# untitled.net
KiCad netlist of a schematic drawn in EAGLE
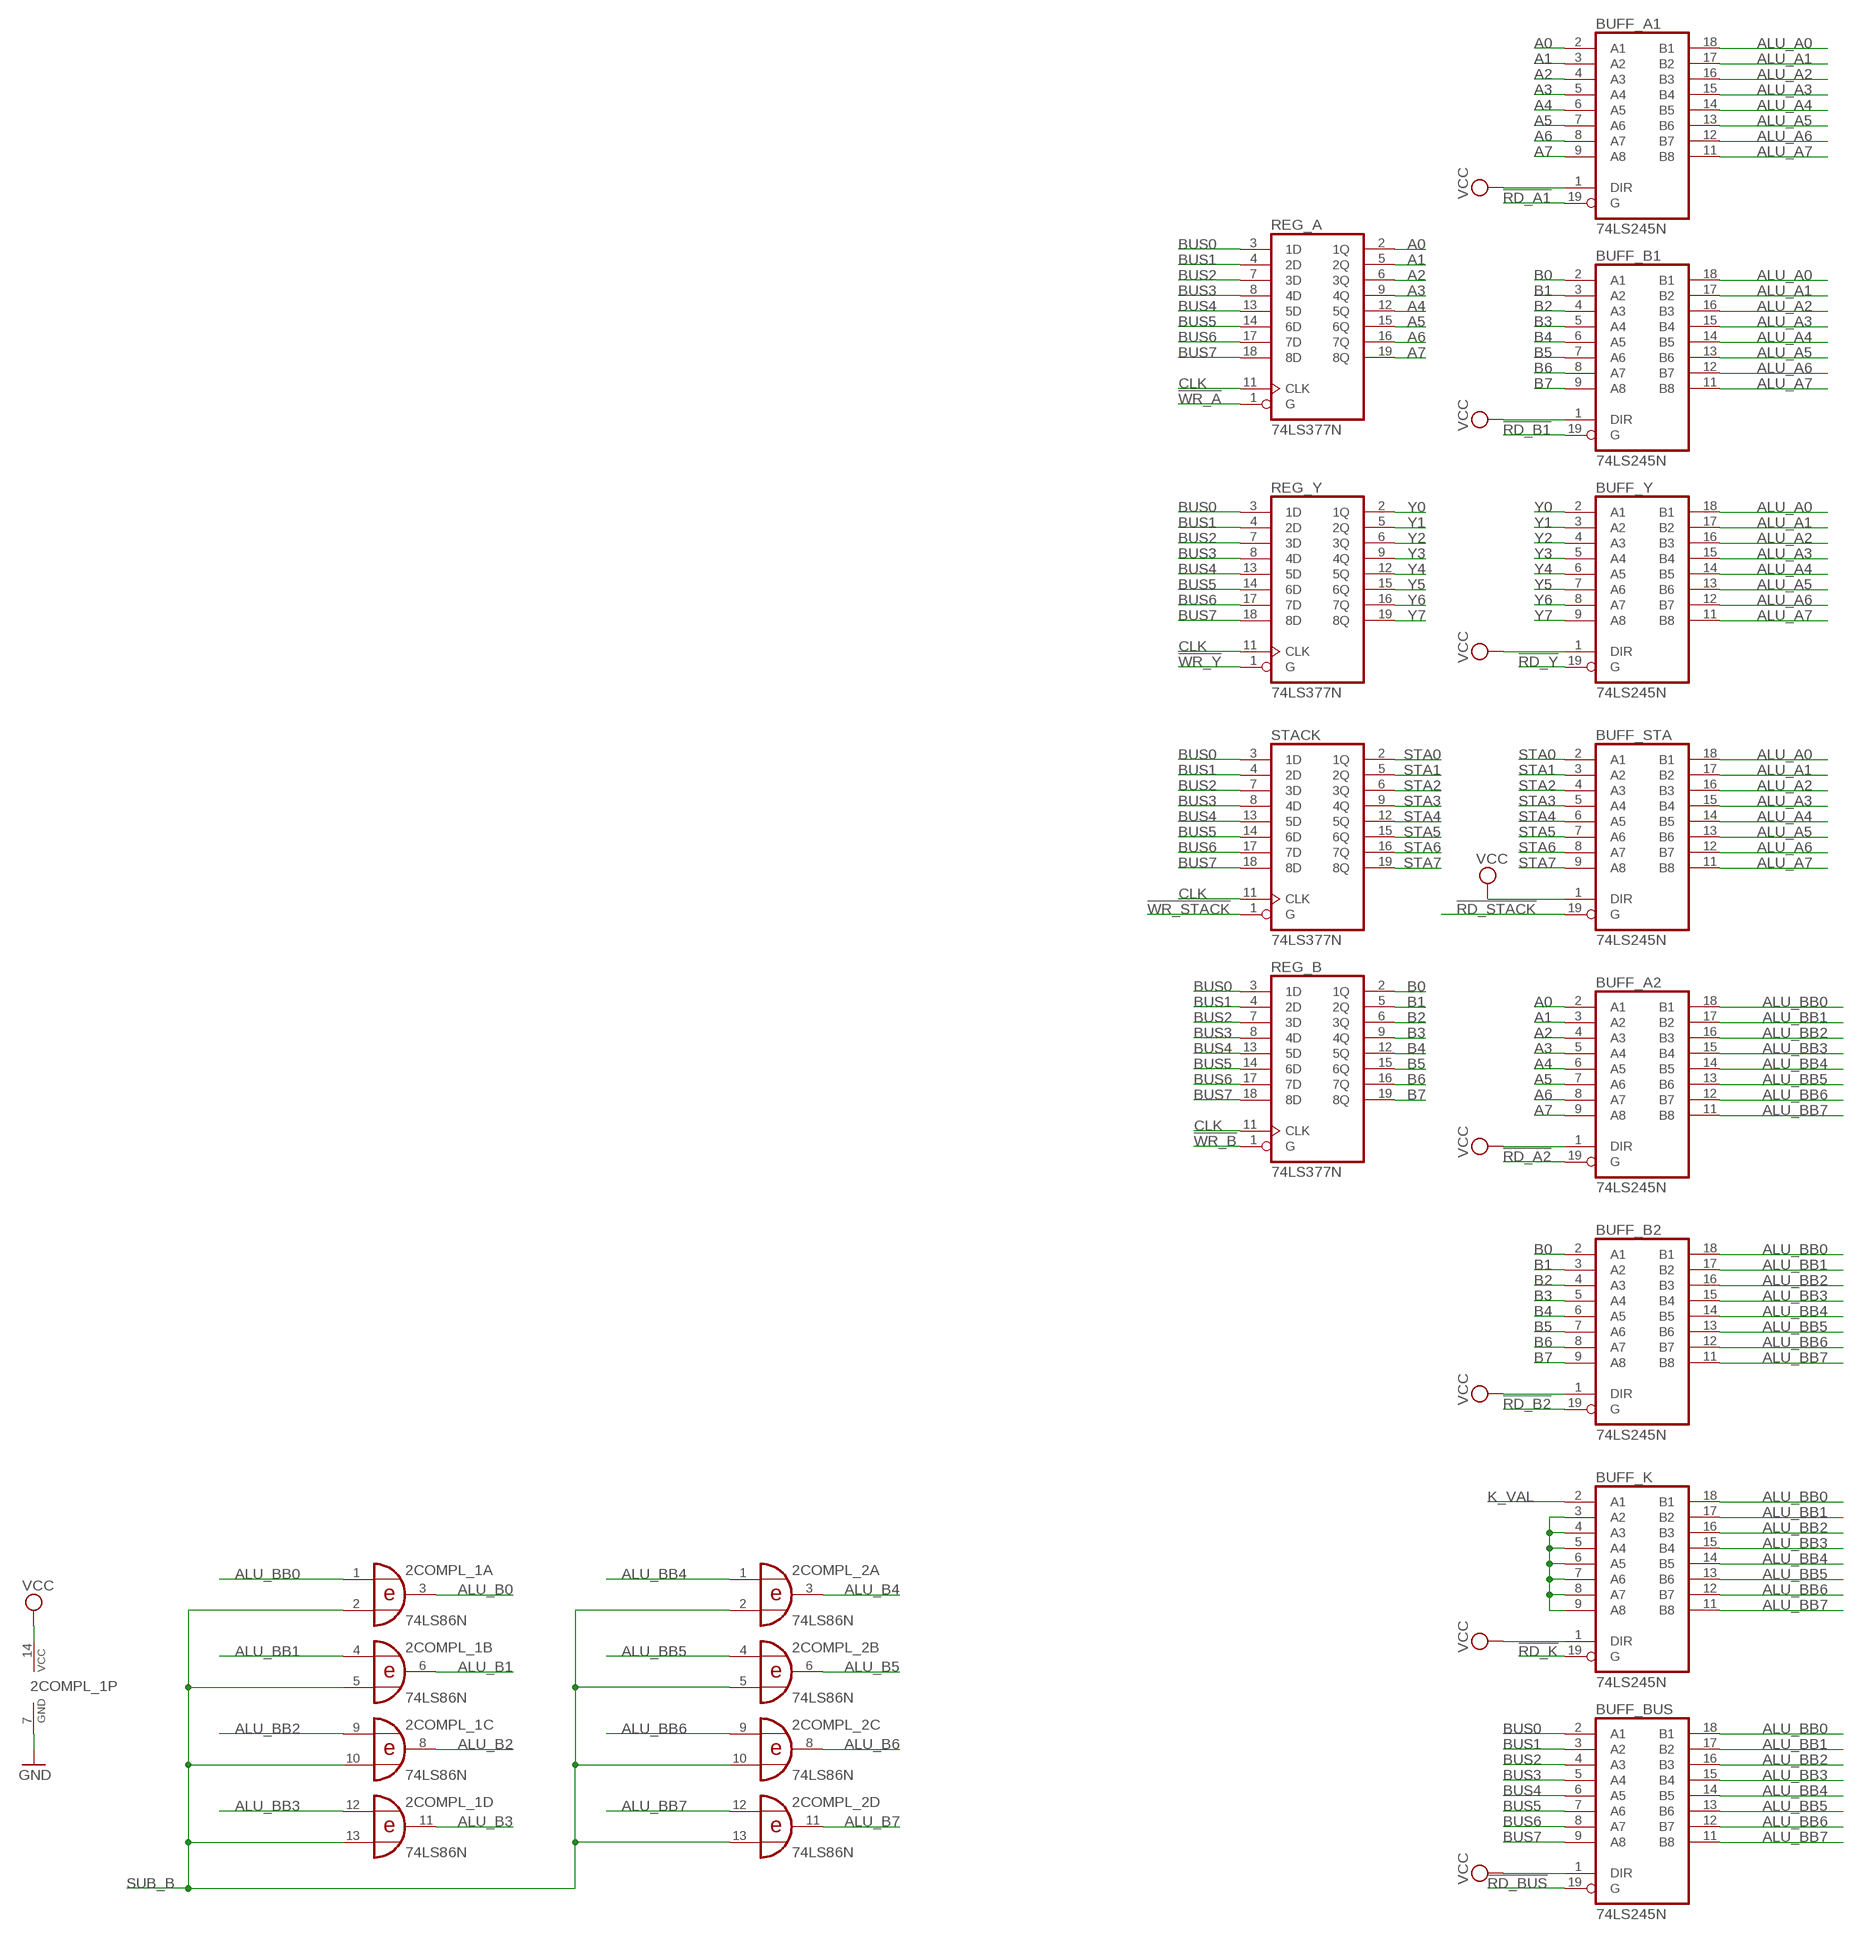
[diagram p0: schematic, sheet 1, part 1 of 2]
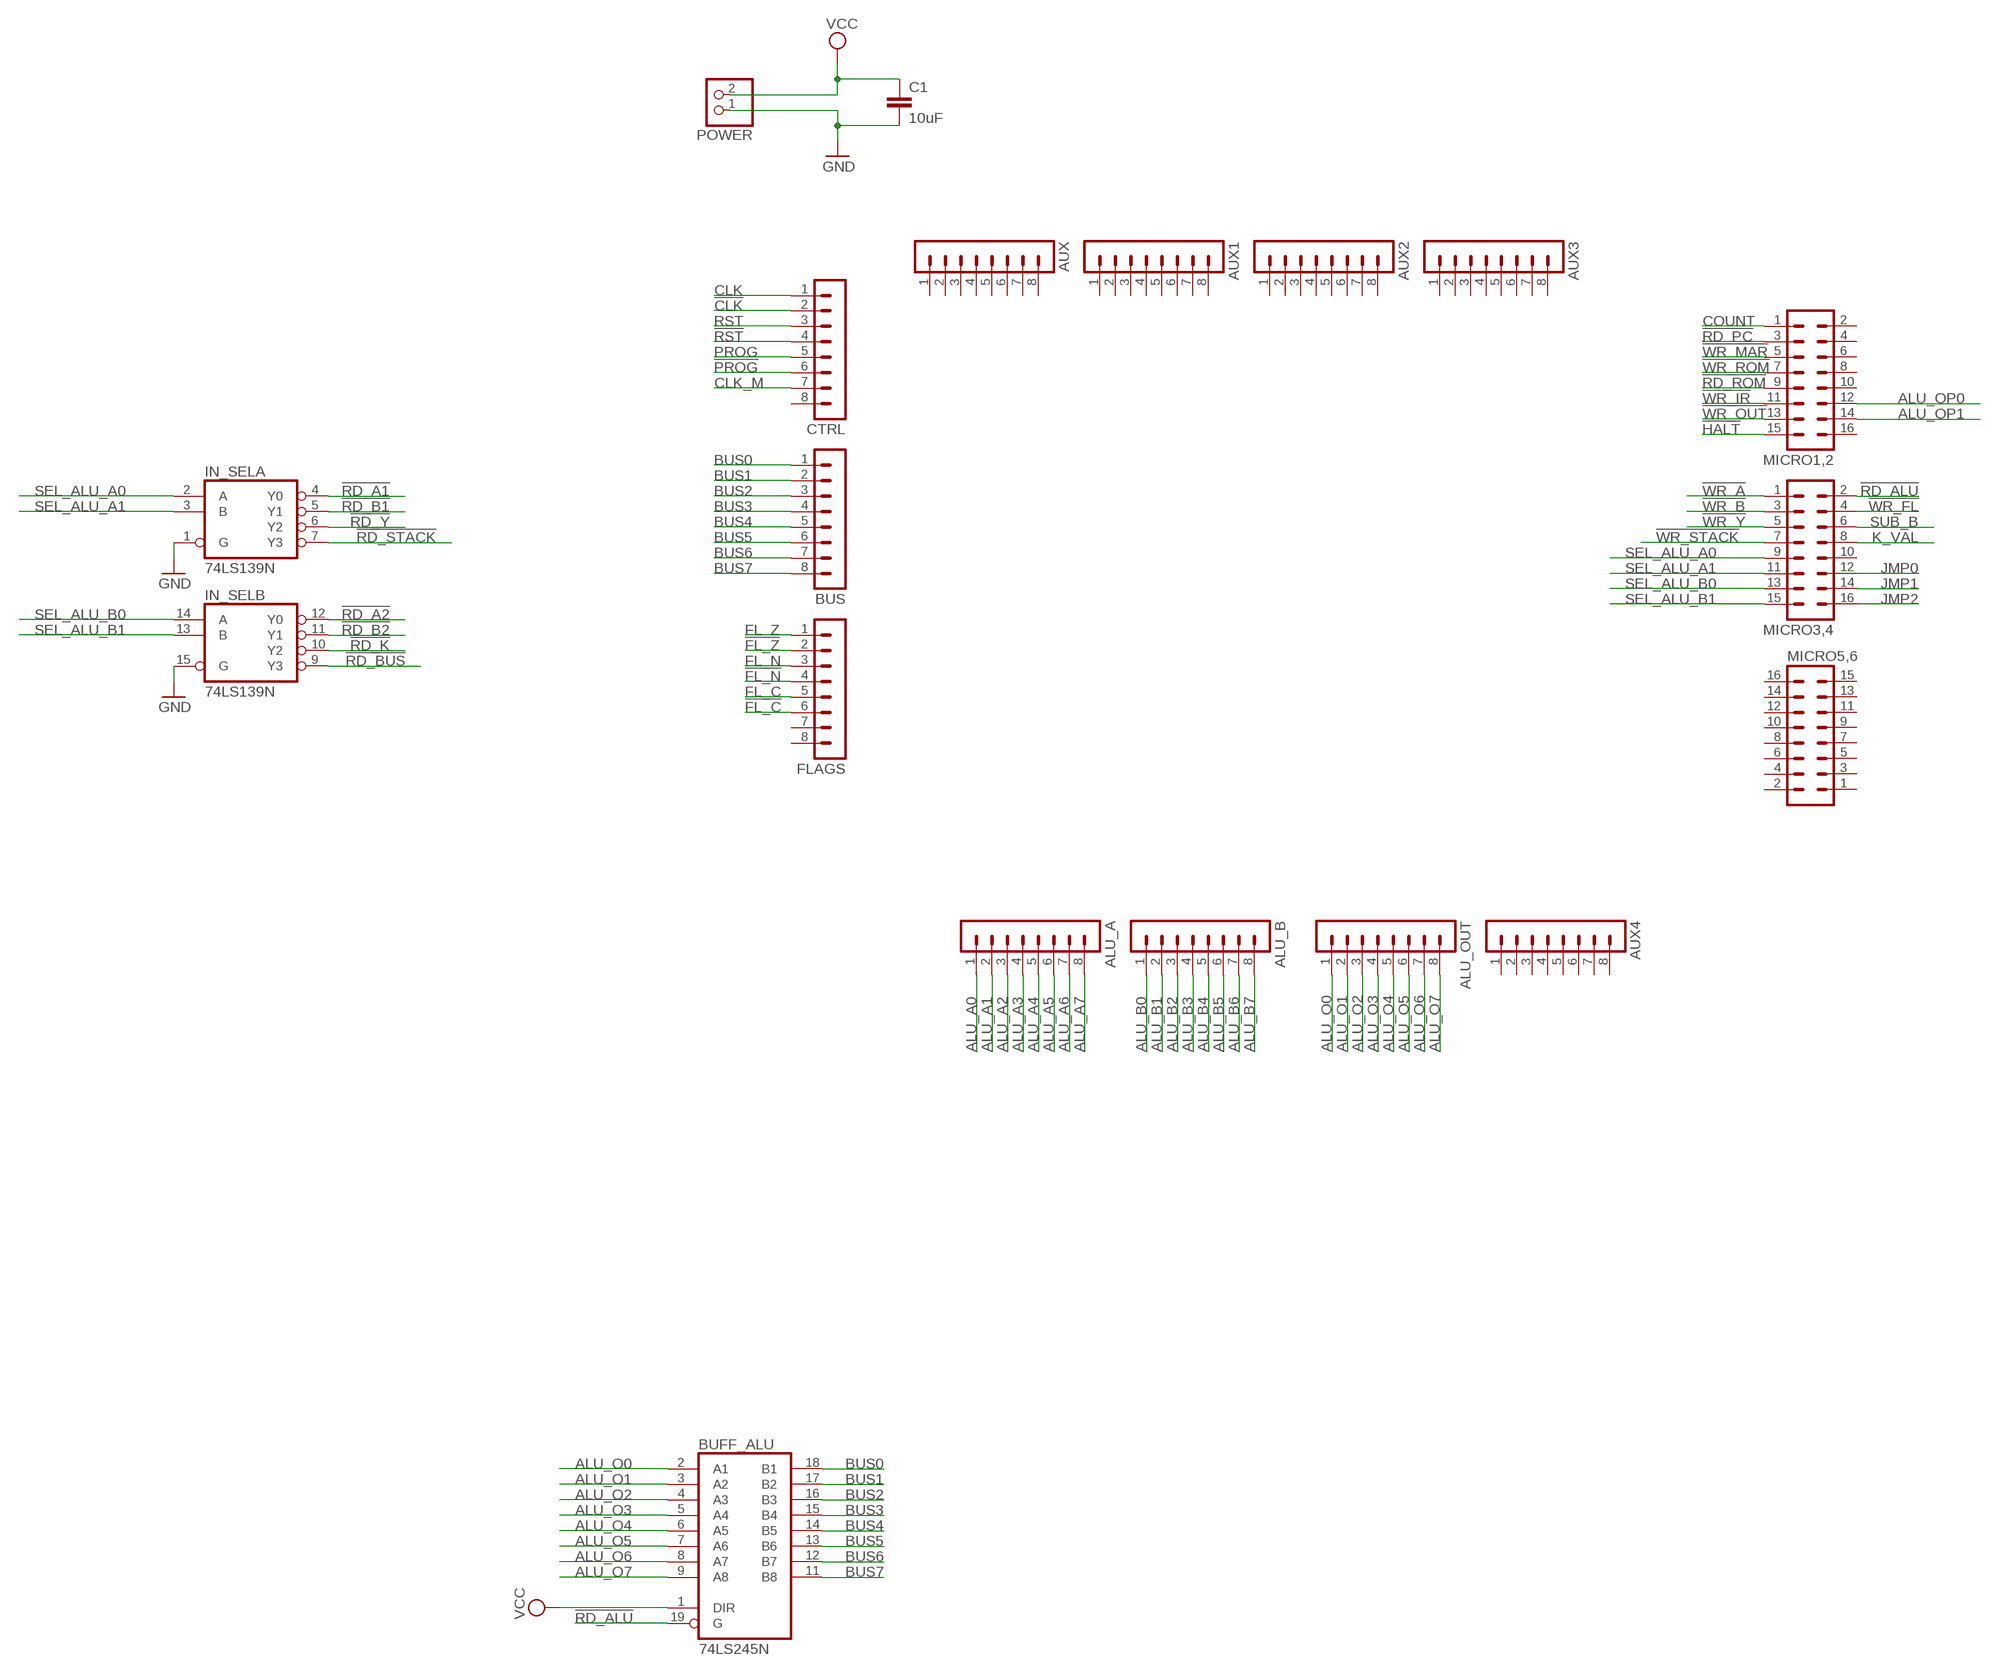
[diagram p1: schematic, sheet 1, part 2 of 2]

(export (version "E")
  (design (tool "Eeschema 10.0.6"))
  (components
    (comp (ref "2COMPL_1")
      (value "74LS86N")
      (footprint "eagle-import:DIL14")
      (libsource (lib "eagle-import") (part "7486NLS"))
    )
    (comp (ref "2COMPL_2")
      (value "74LS86N")
      (footprint "eagle-import:DIL14")
      (libsource (lib "eagle-import") (part "7486NLS"))
    )
    (comp (ref "ALU_A")
      (value "MA08-1")
      (footprint "eagle-import:MA08-1")
      (libsource (lib "eagle-import") (part "MA08-1"))
    )
    (comp (ref "ALU_B")
      (value "MA08-1")
      (footprint "eagle-import:MA08-1")
      (libsource (lib "eagle-import") (part "MA08-1"))
    )
    (comp (ref "ALU_OUT")
      (value "MA08-1")
      (footprint "eagle-import:MA08-1")
      (libsource (lib "eagle-import") (part "MA08-1"))
    )
    (comp (ref "AUX")
      (value "MA08-1")
      (footprint "eagle-import:MA08-1")
      (libsource (lib "eagle-import") (part "MA08-1"))
    )
    (comp (ref "AUX1")
      (value "MA08-1")
      (footprint "eagle-import:MA08-1")
      (libsource (lib "eagle-import") (part "MA08-1"))
    )
    (comp (ref "AUX2")
      (value "MA08-1")
      (footprint "eagle-import:MA08-1")
      (libsource (lib "eagle-import") (part "MA08-1"))
    )
    (comp (ref "AUX3")
      (value "MA08-1")
      (footprint "eagle-import:MA08-1")
      (libsource (lib "eagle-import") (part "MA08-1"))
    )
    (comp (ref "AUX4")
      (value "MA08-1")
      (footprint "eagle-import:MA08-1")
      (libsource (lib "eagle-import") (part "MA08-1"))
    )
    (comp (ref "BUFF_A1")
      (value "74LS245N")
      (footprint "eagle-import:DIL20")
      (libsource (lib "eagle-import") (part "74245NLS"))
    )
    (comp (ref "BUFF_A2")
      (value "74LS245N")
      (footprint "eagle-import:DIL20")
      (libsource (lib "eagle-import") (part "74245NLS"))
    )
    (comp (ref "BUFF_ALU")
      (value "74LS245N")
      (footprint "eagle-import:DIL20")
      (libsource (lib "eagle-import") (part "74245NLS"))
    )
    (comp (ref "BUFF_B1")
      (value "74LS245N")
      (footprint "eagle-import:DIL20")
      (libsource (lib "eagle-import") (part "74245NLS"))
    )
    (comp (ref "BUFF_B2")
      (value "74LS245N")
      (footprint "eagle-import:DIL20")
      (libsource (lib "eagle-import") (part "74245NLS"))
    )
    (comp (ref "BUFF_BUS")
      (value "74LS245N")
      (footprint "eagle-import:DIL20")
      (libsource (lib "eagle-import") (part "74245NLS"))
    )
    (comp (ref "BUFF_K")
      (value "74LS245N")
      (footprint "eagle-import:DIL20")
      (libsource (lib "eagle-import") (part "74245NLS"))
    )
    (comp (ref "BUFF_STA")
      (value "74LS245N")
      (footprint "eagle-import:DIL20")
      (libsource (lib "eagle-import") (part "74245NLS"))
    )
    (comp (ref "BUFF_Y")
      (value "74LS245N")
      (footprint "eagle-import:DIL20")
      (libsource (lib "eagle-import") (part "74245NLS"))
    )
    (comp (ref "BUS")
      (value "MA08-1")
      (footprint "eagle-import:MA08-1")
      (libsource (lib "eagle-import") (part "MA08-1"))
    )
    (comp (ref "C1")
      (value "10uF")
      (footprint "eagle-import:C025-050X050")
      (libsource (lib "eagle-import") (part "C-EU025-050X050"))
    )
    (comp (ref "CTRL")
      (value "MA08-1")
      (footprint "eagle-import:MA08-1")
      (libsource (lib "eagle-import") (part "MA08-1"))
    )
    (comp (ref "FLAGS")
      (value "MA08-1")
      (footprint "eagle-import:MA08-1")
      (libsource (lib "eagle-import") (part "MA08-1"))
    )
    (comp (ref "IN_SEL")
      (value "74LS139N")
      (footprint "eagle-import:DIL16")
      (libsource (lib "eagle-import") (part "74139NLS"))
    )
    (comp (ref "MICRO1,2")
      (value "MA08-2")
      (footprint "eagle-import:MA08-2")
      (libsource (lib "eagle-import") (part "MA08-2"))
    )
    (comp (ref "MICRO3,4")
      (value "MA08-2")
      (footprint "eagle-import:MA08-2")
      (libsource (lib "eagle-import") (part "MA08-2"))
    )
    (comp (ref "MICRO5,6")
      (value "MA08-2")
      (footprint "eagle-import:MA08-2")
      (libsource (lib "eagle-import") (part "MA08-2"))
    )
    (comp (ref "POWER")
      (value "PINHD-1X2")
      (footprint "eagle-import:1X02")
      (libsource (lib "eagle-import") (part "PINHD-1X2"))
    )
    (comp (ref "REG_A")
      (value "74LS377N")
      (footprint "eagle-import:DIL20")
      (libsource (lib "eagle-import") (part "74377NLS"))
    )
    (comp (ref "REG_B")
      (value "74LS377N")
      (footprint "eagle-import:DIL20")
      (libsource (lib "eagle-import") (part "74377NLS"))
    )
    (comp (ref "REG_Y")
      (value "74LS377N")
      (footprint "eagle-import:DIL20")
      (libsource (lib "eagle-import") (part "74377NLS"))
    )
    (comp (ref "STACK")
      (value "74LS377N")
      (footprint "eagle-import:DIL20")
      (libsource (lib "eagle-import") (part "74377NLS"))
    )
  )
  (nets
    (net (code "1") (name "A0") (class "Default")
      (node (ref "BUFF_A1") (pin "2") (pinfunction "A1_2") (pintype "bidirectional"))
      (node (ref "BUFF_A2") (pin "2") (pinfunction "A1_2") (pintype "bidirectional"))
      (node (ref "REG_A") (pin "2") (pinfunction "1Q_2") (pintype "output"))
    )
    (net (code "2") (name "A1") (class "Default")
      (node (ref "BUFF_A1") (pin "3") (pinfunction "A2_3") (pintype "bidirectional"))
      (node (ref "BUFF_A2") (pin "3") (pinfunction "A2_3") (pintype "bidirectional"))
      (node (ref "REG_A") (pin "5") (pinfunction "2Q_5") (pintype "output"))
    )
    (net (code "3") (name "A2") (class "Default")
      (node (ref "BUFF_A1") (pin "4") (pinfunction "A3_4") (pintype "bidirectional"))
      (node (ref "BUFF_A2") (pin "4") (pinfunction "A3_4") (pintype "bidirectional"))
      (node (ref "REG_A") (pin "6") (pinfunction "3Q_6") (pintype "output"))
    )
    (net (code "4") (name "A3") (class "Default")
      (node (ref "BUFF_A1") (pin "5") (pinfunction "A4_5") (pintype "bidirectional"))
      (node (ref "BUFF_A2") (pin "5") (pinfunction "A4_5") (pintype "bidirectional"))
      (node (ref "REG_A") (pin "9") (pinfunction "4Q_9") (pintype "output"))
    )
    (net (code "5") (name "A4") (class "Default")
      (node (ref "BUFF_A1") (pin "6") (pinfunction "A5_6") (pintype "bidirectional"))
      (node (ref "BUFF_A2") (pin "6") (pinfunction "A5_6") (pintype "bidirectional"))
      (node (ref "REG_A") (pin "12") (pinfunction "5Q_12") (pintype "output"))
    )
    (net (code "6") (name "A5") (class "Default")
      (node (ref "BUFF_A1") (pin "7") (pinfunction "A6_7") (pintype "bidirectional"))
      (node (ref "BUFF_A2") (pin "7") (pinfunction "A6_7") (pintype "bidirectional"))
      (node (ref "REG_A") (pin "15") (pinfunction "6Q_15") (pintype "output"))
    )
    (net (code "7") (name "A6") (class "Default")
      (node (ref "BUFF_A1") (pin "8") (pinfunction "A7_8") (pintype "bidirectional"))
      (node (ref "BUFF_A2") (pin "8") (pinfunction "A7_8") (pintype "bidirectional"))
      (node (ref "REG_A") (pin "16") (pinfunction "7Q_16") (pintype "output"))
    )
    (net (code "8") (name "A7") (class "Default")
      (node (ref "BUFF_A1") (pin "9") (pinfunction "A8_9") (pintype "bidirectional"))
      (node (ref "BUFF_A2") (pin "9") (pinfunction "A8_9") (pintype "bidirectional"))
      (node (ref "REG_A") (pin "19") (pinfunction "8Q_19") (pintype "output"))
    )
    (net (code "9") (name "ALU_A0") (class "Default")
      (node (ref "ALU_A") (pin "1") (pinfunction "1_1") (pintype "passive"))
      (node (ref "BUFF_A1") (pin "18") (pinfunction "B1_18") (pintype "bidirectional"))
      (node (ref "BUFF_B1") (pin "18") (pinfunction "B1_18") (pintype "bidirectional"))
      (node (ref "BUFF_STA") (pin "18") (pinfunction "B1_18") (pintype "bidirectional"))
      (node (ref "BUFF_Y") (pin "18") (pinfunction "B1_18") (pintype "bidirectional"))
    )
    (net (code "10") (name "ALU_A1") (class "Default")
      (node (ref "ALU_A") (pin "2") (pinfunction "2_2") (pintype "passive"))
      (node (ref "BUFF_A1") (pin "17") (pinfunction "B2_17") (pintype "bidirectional"))
      (node (ref "BUFF_B1") (pin "17") (pinfunction "B2_17") (pintype "bidirectional"))
      (node (ref "BUFF_STA") (pin "17") (pinfunction "B2_17") (pintype "bidirectional"))
      (node (ref "BUFF_Y") (pin "17") (pinfunction "B2_17") (pintype "bidirectional"))
    )
    (net (code "11") (name "ALU_A2") (class "Default")
      (node (ref "ALU_A") (pin "3") (pinfunction "3_3") (pintype "passive"))
      (node (ref "BUFF_A1") (pin "16") (pinfunction "B3_16") (pintype "bidirectional"))
      (node (ref "BUFF_B1") (pin "16") (pinfunction "B3_16") (pintype "bidirectional"))
      (node (ref "BUFF_STA") (pin "16") (pinfunction "B3_16") (pintype "bidirectional"))
      (node (ref "BUFF_Y") (pin "16") (pinfunction "B3_16") (pintype "bidirectional"))
    )
    (net (code "12") (name "ALU_A3") (class "Default")
      (node (ref "ALU_A") (pin "4") (pinfunction "4_4") (pintype "passive"))
      (node (ref "BUFF_A1") (pin "15") (pinfunction "B4_15") (pintype "bidirectional"))
      (node (ref "BUFF_B1") (pin "15") (pinfunction "B4_15") (pintype "bidirectional"))
      (node (ref "BUFF_STA") (pin "15") (pinfunction "B4_15") (pintype "bidirectional"))
      (node (ref "BUFF_Y") (pin "15") (pinfunction "B4_15") (pintype "bidirectional"))
    )
    (net (code "13") (name "ALU_A4") (class "Default")
      (node (ref "ALU_A") (pin "5") (pinfunction "5_5") (pintype "passive"))
      (node (ref "BUFF_A1") (pin "14") (pinfunction "B5_14") (pintype "bidirectional"))
      (node (ref "BUFF_B1") (pin "14") (pinfunction "B5_14") (pintype "bidirectional"))
      (node (ref "BUFF_STA") (pin "14") (pinfunction "B5_14") (pintype "bidirectional"))
      (node (ref "BUFF_Y") (pin "14") (pinfunction "B5_14") (pintype "bidirectional"))
    )
    (net (code "14") (name "ALU_A5") (class "Default")
      (node (ref "ALU_A") (pin "6") (pinfunction "6_6") (pintype "passive"))
      (node (ref "BUFF_A1") (pin "13") (pinfunction "B6_13") (pintype "bidirectional"))
      (node (ref "BUFF_B1") (pin "13") (pinfunction "B6_13") (pintype "bidirectional"))
      (node (ref "BUFF_STA") (pin "13") (pinfunction "B6_13") (pintype "bidirectional"))
      (node (ref "BUFF_Y") (pin "13") (pinfunction "B6_13") (pintype "bidirectional"))
    )
    (net (code "15") (name "ALU_A6") (class "Default")
      (node (ref "ALU_A") (pin "7") (pinfunction "7_7") (pintype "passive"))
      (node (ref "BUFF_A1") (pin "12") (pinfunction "B7_12") (pintype "bidirectional"))
      (node (ref "BUFF_B1") (pin "12") (pinfunction "B7_12") (pintype "bidirectional"))
      (node (ref "BUFF_STA") (pin "12") (pinfunction "B7_12") (pintype "bidirectional"))
      (node (ref "BUFF_Y") (pin "12") (pinfunction "B7_12") (pintype "bidirectional"))
    )
    (net (code "16") (name "ALU_A7") (class "Default")
      (node (ref "ALU_A") (pin "8") (pinfunction "8_8") (pintype "passive"))
      (node (ref "BUFF_A1") (pin "11") (pinfunction "B8_11") (pintype "bidirectional"))
      (node (ref "BUFF_B1") (pin "11") (pinfunction "B8_11") (pintype "bidirectional"))
      (node (ref "BUFF_STA") (pin "11") (pinfunction "B8_11") (pintype "bidirectional"))
      (node (ref "BUFF_Y") (pin "11") (pinfunction "B8_11") (pintype "bidirectional"))
    )
    (net (code "17") (name "ALU_B0") (class "Default")
      (node (ref "2COMPL_1") (pin "3") (pinfunction "O_3") (pintype "output"))
      (node (ref "ALU_B") (pin "1") (pinfunction "1_1") (pintype "passive"))
    )
    (net (code "18") (name "ALU_B1") (class "Default")
      (node (ref "2COMPL_1") (pin "6") (pinfunction "O_6") (pintype "output"))
      (node (ref "ALU_B") (pin "2") (pinfunction "2_2") (pintype "passive"))
    )
    (net (code "19") (name "ALU_B2") (class "Default")
      (node (ref "2COMPL_1") (pin "8") (pinfunction "O_8") (pintype "output"))
      (node (ref "ALU_B") (pin "3") (pinfunction "3_3") (pintype "passive"))
    )
    (net (code "20") (name "ALU_B3") (class "Default")
      (node (ref "2COMPL_1") (pin "11") (pinfunction "O_11") (pintype "output"))
      (node (ref "ALU_B") (pin "4") (pinfunction "4_4") (pintype "passive"))
    )
    (net (code "21") (name "ALU_B4") (class "Default")
      (node (ref "2COMPL_2") (pin "3") (pinfunction "O_3") (pintype "output"))
      (node (ref "ALU_B") (pin "5") (pinfunction "5_5") (pintype "passive"))
    )
    (net (code "22") (name "ALU_B5") (class "Default")
      (node (ref "2COMPL_2") (pin "6") (pinfunction "O_6") (pintype "output"))
      (node (ref "ALU_B") (pin "6") (pinfunction "6_6") (pintype "passive"))
    )
    (net (code "23") (name "ALU_B6") (class "Default")
      (node (ref "2COMPL_2") (pin "8") (pinfunction "O_8") (pintype "output"))
      (node (ref "ALU_B") (pin "7") (pinfunction "7_7") (pintype "passive"))
    )
    (net (code "24") (name "ALU_B7") (class "Default")
      (node (ref "2COMPL_2") (pin "11") (pinfunction "O_11") (pintype "output"))
      (node (ref "ALU_B") (pin "8") (pinfunction "8_8") (pintype "passive"))
    )
    (net (code "25") (name "ALU_BB0") (class "Default")
      (node (ref "2COMPL_1") (pin "1") (pinfunction "I0_1") (pintype "input"))
      (node (ref "BUFF_A2") (pin "18") (pinfunction "B1_18") (pintype "bidirectional"))
      (node (ref "BUFF_B2") (pin "18") (pinfunction "B1_18") (pintype "bidirectional"))
      (node (ref "BUFF_BUS") (pin "18") (pinfunction "B1_18") (pintype "bidirectional"))
      (node (ref "BUFF_K") (pin "18") (pinfunction "B1_18") (pintype "bidirectional"))
    )
    (net (code "26") (name "ALU_BB1") (class "Default")
      (node (ref "2COMPL_1") (pin "4") (pinfunction "I0_4") (pintype "input"))
      (node (ref "BUFF_A2") (pin "17") (pinfunction "B2_17") (pintype "bidirectional"))
      (node (ref "BUFF_B2") (pin "17") (pinfunction "B2_17") (pintype "bidirectional"))
      (node (ref "BUFF_BUS") (pin "17") (pinfunction "B2_17") (pintype "bidirectional"))
      (node (ref "BUFF_K") (pin "17") (pinfunction "B2_17") (pintype "bidirectional"))
    )
    (net (code "27") (name "ALU_BB2") (class "Default")
      (node (ref "2COMPL_1") (pin "9") (pinfunction "I0_9") (pintype "input"))
      (node (ref "BUFF_A2") (pin "16") (pinfunction "B3_16") (pintype "bidirectional"))
      (node (ref "BUFF_B2") (pin "16") (pinfunction "B3_16") (pintype "bidirectional"))
      (node (ref "BUFF_BUS") (pin "16") (pinfunction "B3_16") (pintype "bidirectional"))
      (node (ref "BUFF_K") (pin "16") (pinfunction "B3_16") (pintype "bidirectional"))
    )
    (net (code "28") (name "ALU_BB3") (class "Default")
      (node (ref "2COMPL_1") (pin "12") (pinfunction "I0_12") (pintype "input"))
      (node (ref "BUFF_A2") (pin "15") (pinfunction "B4_15") (pintype "bidirectional"))
      (node (ref "BUFF_B2") (pin "15") (pinfunction "B4_15") (pintype "bidirectional"))
      (node (ref "BUFF_BUS") (pin "15") (pinfunction "B4_15") (pintype "bidirectional"))
      (node (ref "BUFF_K") (pin "15") (pinfunction "B4_15") (pintype "bidirectional"))
    )
    (net (code "29") (name "ALU_BB4") (class "Default")
      (node (ref "2COMPL_2") (pin "1") (pinfunction "I0_1") (pintype "input"))
      (node (ref "BUFF_A2") (pin "14") (pinfunction "B5_14") (pintype "bidirectional"))
      (node (ref "BUFF_B2") (pin "14") (pinfunction "B5_14") (pintype "bidirectional"))
      (node (ref "BUFF_BUS") (pin "14") (pinfunction "B5_14") (pintype "bidirectional"))
      (node (ref "BUFF_K") (pin "14") (pinfunction "B5_14") (pintype "bidirectional"))
    )
    (net (code "30") (name "ALU_BB5") (class "Default")
      (node (ref "2COMPL_2") (pin "4") (pinfunction "I0_4") (pintype "input"))
      (node (ref "BUFF_A2") (pin "13") (pinfunction "B6_13") (pintype "bidirectional"))
      (node (ref "BUFF_B2") (pin "13") (pinfunction "B6_13") (pintype "bidirectional"))
      (node (ref "BUFF_BUS") (pin "13") (pinfunction "B6_13") (pintype "bidirectional"))
      (node (ref "BUFF_K") (pin "13") (pinfunction "B6_13") (pintype "bidirectional"))
    )
    (net (code "31") (name "ALU_BB6") (class "Default")
      (node (ref "2COMPL_2") (pin "9") (pinfunction "I0_9") (pintype "input"))
      (node (ref "BUFF_A2") (pin "12") (pinfunction "B7_12") (pintype "bidirectional"))
      (node (ref "BUFF_B2") (pin "12") (pinfunction "B7_12") (pintype "bidirectional"))
      (node (ref "BUFF_BUS") (pin "12") (pinfunction "B7_12") (pintype "bidirectional"))
      (node (ref "BUFF_K") (pin "12") (pinfunction "B7_12") (pintype "bidirectional"))
    )
    (net (code "32") (name "ALU_BB7") (class "Default")
      (node (ref "2COMPL_2") (pin "12") (pinfunction "I0_12") (pintype "input"))
      (node (ref "BUFF_A2") (pin "11") (pinfunction "B8_11") (pintype "bidirectional"))
      (node (ref "BUFF_B2") (pin "11") (pinfunction "B8_11") (pintype "bidirectional"))
      (node (ref "BUFF_BUS") (pin "11") (pinfunction "B8_11") (pintype "bidirectional"))
      (node (ref "BUFF_K") (pin "11") (pinfunction "B8_11") (pintype "bidirectional"))
    )
    (net (code "33") (name "ALU_O0") (class "Default")
      (node (ref "ALU_OUT") (pin "1") (pinfunction "1_1") (pintype "passive"))
      (node (ref "BUFF_ALU") (pin "2") (pinfunction "A1_2") (pintype "bidirectional"))
    )
    (net (code "34") (name "ALU_O1") (class "Default")
      (node (ref "ALU_OUT") (pin "2") (pinfunction "2_2") (pintype "passive"))
      (node (ref "BUFF_ALU") (pin "3") (pinfunction "A2_3") (pintype "bidirectional"))
    )
    (net (code "35") (name "ALU_O2") (class "Default")
      (node (ref "ALU_OUT") (pin "3") (pinfunction "3_3") (pintype "passive"))
      (node (ref "BUFF_ALU") (pin "4") (pinfunction "A3_4") (pintype "bidirectional"))
    )
    (net (code "36") (name "ALU_O3") (class "Default")
      (node (ref "ALU_OUT") (pin "4") (pinfunction "4_4") (pintype "passive"))
      (node (ref "BUFF_ALU") (pin "5") (pinfunction "A4_5") (pintype "bidirectional"))
    )
    (net (code "37") (name "ALU_O4") (class "Default")
      (node (ref "ALU_OUT") (pin "5") (pinfunction "5_5") (pintype "passive"))
      (node (ref "BUFF_ALU") (pin "6") (pinfunction "A5_6") (pintype "bidirectional"))
    )
    (net (code "38") (name "ALU_O5") (class "Default")
      (node (ref "ALU_OUT") (pin "6") (pinfunction "6_6") (pintype "passive"))
      (node (ref "BUFF_ALU") (pin "7") (pinfunction "A6_7") (pintype "bidirectional"))
    )
    (net (code "39") (name "ALU_O6") (class "Default")
      (node (ref "ALU_OUT") (pin "7") (pinfunction "7_7") (pintype "passive"))
      (node (ref "BUFF_ALU") (pin "8") (pinfunction "A7_8") (pintype "bidirectional"))
    )
    (net (code "40") (name "ALU_O7") (class "Default")
      (node (ref "ALU_OUT") (pin "8") (pinfunction "8_8") (pintype "passive"))
      (node (ref "BUFF_ALU") (pin "9") (pinfunction "A8_9") (pintype "bidirectional"))
    )
    (net (code "41") (name "ALU_OP0") (class "Default")
      (node (ref "MICRO1,2") (pin "12") (pinfunction "12_12") (pintype "passive"))
    )
    (net (code "42") (name "ALU_OP1") (class "Default")
      (node (ref "MICRO1,2") (pin "14") (pinfunction "14_14") (pintype "passive"))
    )
    (net (code "43") (name "B0") (class "Default")
      (node (ref "BUFF_B1") (pin "2") (pinfunction "A1_2") (pintype "bidirectional"))
      (node (ref "BUFF_B2") (pin "2") (pinfunction "A1_2") (pintype "bidirectional"))
      (node (ref "REG_B") (pin "2") (pinfunction "1Q_2") (pintype "output"))
    )
    (net (code "44") (name "B1") (class "Default")
      (node (ref "BUFF_B1") (pin "3") (pinfunction "A2_3") (pintype "bidirectional"))
      (node (ref "BUFF_B2") (pin "3") (pinfunction "A2_3") (pintype "bidirectional"))
      (node (ref "REG_B") (pin "5") (pinfunction "2Q_5") (pintype "output"))
    )
    (net (code "45") (name "B2") (class "Default")
      (node (ref "BUFF_B1") (pin "4") (pinfunction "A3_4") (pintype "bidirectional"))
      (node (ref "BUFF_B2") (pin "4") (pinfunction "A3_4") (pintype "bidirectional"))
      (node (ref "REG_B") (pin "6") (pinfunction "3Q_6") (pintype "output"))
    )
    (net (code "46") (name "B3") (class "Default")
      (node (ref "BUFF_B1") (pin "5") (pinfunction "A4_5") (pintype "bidirectional"))
      (node (ref "BUFF_B2") (pin "5") (pinfunction "A4_5") (pintype "bidirectional"))
      (node (ref "REG_B") (pin "9") (pinfunction "4Q_9") (pintype "output"))
    )
    (net (code "47") (name "B4") (class "Default")
      (node (ref "BUFF_B1") (pin "6") (pinfunction "A5_6") (pintype "bidirectional"))
      (node (ref "BUFF_B2") (pin "6") (pinfunction "A5_6") (pintype "bidirectional"))
      (node (ref "REG_B") (pin "12") (pinfunction "5Q_12") (pintype "output"))
    )
    (net (code "48") (name "B5") (class "Default")
      (node (ref "BUFF_B1") (pin "7") (pinfunction "A6_7") (pintype "bidirectional"))
      (node (ref "BUFF_B2") (pin "7") (pinfunction "A6_7") (pintype "bidirectional"))
      (node (ref "REG_B") (pin "15") (pinfunction "6Q_15") (pintype "output"))
    )
    (net (code "49") (name "B6") (class "Default")
      (node (ref "BUFF_B1") (pin "8") (pinfunction "A7_8") (pintype "bidirectional"))
      (node (ref "BUFF_B2") (pin "8") (pinfunction "A7_8") (pintype "bidirectional"))
      (node (ref "REG_B") (pin "16") (pinfunction "7Q_16") (pintype "output"))
    )
    (net (code "50") (name "B7") (class "Default")
      (node (ref "BUFF_B1") (pin "9") (pinfunction "A8_9") (pintype "bidirectional"))
      (node (ref "BUFF_B2") (pin "9") (pinfunction "A8_9") (pintype "bidirectional"))
      (node (ref "REG_B") (pin "19") (pinfunction "8Q_19") (pintype "output"))
    )
    (net (code "51") (name "BUS0") (class "Default")
      (node (ref "BUFF_ALU") (pin "18") (pinfunction "B1_18") (pintype "bidirectional"))
      (node (ref "BUFF_BUS") (pin "2") (pinfunction "A1_2") (pintype "bidirectional"))
      (node (ref "BUS") (pin "1") (pinfunction "1_1") (pintype "passive"))
      (node (ref "REG_A") (pin "3") (pinfunction "1D_3") (pintype "input"))
      (node (ref "REG_B") (pin "3") (pinfunction "1D_3") (pintype "input"))
      (node (ref "REG_Y") (pin "3") (pinfunction "1D_3") (pintype "input"))
      (node (ref "STACK") (pin "3") (pinfunction "1D_3") (pintype "input"))
    )
    (net (code "52") (name "BUS1") (class "Default")
      (node (ref "BUFF_ALU") (pin "17") (pinfunction "B2_17") (pintype "bidirectional"))
      (node (ref "BUFF_BUS") (pin "3") (pinfunction "A2_3") (pintype "bidirectional"))
      (node (ref "BUS") (pin "2") (pinfunction "2_2") (pintype "passive"))
      (node (ref "REG_A") (pin "4") (pinfunction "2D_4") (pintype "input"))
      (node (ref "REG_B") (pin "4") (pinfunction "2D_4") (pintype "input"))
      (node (ref "REG_Y") (pin "4") (pinfunction "2D_4") (pintype "input"))
      (node (ref "STACK") (pin "4") (pinfunction "2D_4") (pintype "input"))
    )
    (net (code "53") (name "BUS2") (class "Default")
      (node (ref "BUFF_ALU") (pin "16") (pinfunction "B3_16") (pintype "bidirectional"))
      (node (ref "BUFF_BUS") (pin "4") (pinfunction "A3_4") (pintype "bidirectional"))
      (node (ref "BUS") (pin "3") (pinfunction "3_3") (pintype "passive"))
      (node (ref "REG_A") (pin "7") (pinfunction "3D_7") (pintype "input"))
      (node (ref "REG_B") (pin "7") (pinfunction "3D_7") (pintype "input"))
      (node (ref "REG_Y") (pin "7") (pinfunction "3D_7") (pintype "input"))
      (node (ref "STACK") (pin "7") (pinfunction "3D_7") (pintype "input"))
    )
    (net (code "54") (name "BUS3") (class "Default")
      (node (ref "BUFF_ALU") (pin "15") (pinfunction "B4_15") (pintype "bidirectional"))
      (node (ref "BUFF_BUS") (pin "5") (pinfunction "A4_5") (pintype "bidirectional"))
      (node (ref "BUS") (pin "4") (pinfunction "4_4") (pintype "passive"))
      (node (ref "REG_A") (pin "8") (pinfunction "4D_8") (pintype "input"))
      (node (ref "REG_B") (pin "8") (pinfunction "4D_8") (pintype "input"))
      (node (ref "REG_Y") (pin "8") (pinfunction "4D_8") (pintype "input"))
      (node (ref "STACK") (pin "8") (pinfunction "4D_8") (pintype "input"))
    )
    (net (code "55") (name "BUS4") (class "Default")
      (node (ref "BUFF_ALU") (pin "14") (pinfunction "B5_14") (pintype "bidirectional"))
      (node (ref "BUFF_BUS") (pin "6") (pinfunction "A5_6") (pintype "bidirectional"))
      (node (ref "BUS") (pin "5") (pinfunction "5_5") (pintype "passive"))
      (node (ref "REG_A") (pin "13") (pinfunction "5D_13") (pintype "input"))
      (node (ref "REG_B") (pin "13") (pinfunction "5D_13") (pintype "input"))
      (node (ref "REG_Y") (pin "13") (pinfunction "5D_13") (pintype "input"))
      (node (ref "STACK") (pin "13") (pinfunction "5D_13") (pintype "input"))
    )
    (net (code "56") (name "BUS5") (class "Default")
      (node (ref "BUFF_ALU") (pin "13") (pinfunction "B6_13") (pintype "bidirectional"))
      (node (ref "BUFF_BUS") (pin "7") (pinfunction "A6_7") (pintype "bidirectional"))
      (node (ref "BUS") (pin "6") (pinfunction "6_6") (pintype "passive"))
      (node (ref "REG_A") (pin "14") (pinfunction "6D_14") (pintype "input"))
      (node (ref "REG_B") (pin "14") (pinfunction "6D_14") (pintype "input"))
      (node (ref "REG_Y") (pin "14") (pinfunction "6D_14") (pintype "input"))
      (node (ref "STACK") (pin "14") (pinfunction "6D_14") (pintype "input"))
    )
    (net (code "57") (name "BUS6") (class "Default")
      (node (ref "BUFF_ALU") (pin "12") (pinfunction "B7_12") (pintype "bidirectional"))
      (node (ref "BUFF_BUS") (pin "8") (pinfunction "A7_8") (pintype "bidirectional"))
      (node (ref "BUS") (pin "7") (pinfunction "7_7") (pintype "passive"))
      (node (ref "REG_A") (pin "17") (pinfunction "7D_17") (pintype "input"))
      (node (ref "REG_B") (pin "17") (pinfunction "7D_17") (pintype "input"))
      (node (ref "REG_Y") (pin "17") (pinfunction "7D_17") (pintype "input"))
      (node (ref "STACK") (pin "17") (pinfunction "7D_17") (pintype "input"))
    )
    (net (code "58") (name "BUS7") (class "Default")
      (node (ref "BUFF_ALU") (pin "11") (pinfunction "B8_11") (pintype "bidirectional"))
      (node (ref "BUFF_BUS") (pin "9") (pinfunction "A8_9") (pintype "bidirectional"))
      (node (ref "BUS") (pin "8") (pinfunction "8_8") (pintype "passive"))
      (node (ref "REG_A") (pin "18") (pinfunction "8D_18") (pintype "input"))
      (node (ref "REG_B") (pin "18") (pinfunction "8D_18") (pintype "input"))
      (node (ref "REG_Y") (pin "18") (pinfunction "8D_18") (pintype "input"))
      (node (ref "STACK") (pin "18") (pinfunction "8D_18") (pintype "input"))
    )
    (net (code "59") (name "CLK") (class "Default")
      (node (ref "CTRL") (pin "1") (pinfunction "1_1") (pintype "passive"))
      (node (ref "REG_A") (pin "11") (pinfunction "CLK_11") (pintype "input"))
      (node (ref "REG_B") (pin "11") (pinfunction "CLK_11") (pintype "input"))
      (node (ref "REG_Y") (pin "11") (pinfunction "CLK_11") (pintype "input"))
      (node (ref "STACK") (pin "11") (pinfunction "CLK_11") (pintype "input"))
    )
    (net (code "60") (name "CLK_M") (class "Default")
      (node (ref "CTRL") (pin "7") (pinfunction "7_7") (pintype "passive"))
    )
    (net (code "61") (name "COUNT") (class "Default")
      (node (ref "MICRO1,2") (pin "1") (pinfunction "1_1") (pintype "passive"))
    )
    (net (code "62") (name "FL_C") (class "Default")
      (node (ref "FLAGS") (pin "5") (pinfunction "5_5") (pintype "passive"))
    )
    (net (code "63") (name "FL_N") (class "Default")
      (node (ref "FLAGS") (pin "3") (pinfunction "3_3") (pintype "passive"))
    )
    (net (code "64") (name "FL_Z") (class "Default")
      (node (ref "FLAGS") (pin "1") (pinfunction "1_1") (pintype "passive"))
    )
    (net (code "65") (name "GND") (class "Default")
      (node (ref "2COMPL_1") (pin "7") (pinfunction "GND_7") (pintype "power_in"))
      (node (ref "C1") (pin "2") (pinfunction "2_2") (pintype "passive"))
      (node (ref "IN_SEL") (pin "1") (pinfunction "G_1") (pintype "input"))
      (node (ref "IN_SEL") (pin "15") (pinfunction "G_15") (pintype "input"))
      (node (ref "POWER") (pin "1") (pinfunction "1_1") (pintype "passive"))
    )
    (net (code "66") (name "JMP0") (class "Default")
      (node (ref "MICRO3,4") (pin "12") (pinfunction "12_12") (pintype "passive"))
    )
    (net (code "67") (name "JMP1") (class "Default")
      (node (ref "MICRO3,4") (pin "14") (pinfunction "14_14") (pintype "passive"))
    )
    (net (code "68") (name "JMP2") (class "Default")
      (node (ref "MICRO3,4") (pin "16") (pinfunction "16_16") (pintype "passive"))
    )
    (net (code "69") (name "K_VAL") (class "Default")
      (node (ref "BUFF_K") (pin "2") (pinfunction "A1_2") (pintype "bidirectional"))
      (node (ref "MICRO3,4") (pin "8") (pinfunction "8_8") (pintype "passive"))
    )
    (net (code "70") (name "Net-(BUFF_KA-A2)") (class "Default")
      (node (ref "BUFF_K") (pin "3") (pinfunction "A2_3") (pintype "bidirectional"))
      (node (ref "BUFF_K") (pin "4") (pinfunction "A3_4") (pintype "bidirectional"))
      (node (ref "BUFF_K") (pin "5") (pinfunction "A4_5") (pintype "bidirectional"))
      (node (ref "BUFF_K") (pin "6") (pinfunction "A5_6") (pintype "bidirectional"))
      (node (ref "BUFF_K") (pin "7") (pinfunction "A6_7") (pintype "bidirectional"))
      (node (ref "BUFF_K") (pin "8") (pinfunction "A7_8") (pintype "bidirectional"))
      (node (ref "BUFF_K") (pin "9") (pinfunction "A8_9") (pintype "bidirectional"))
    )
    (net (code "71") (name "PROG") (class "Default")
      (node (ref "CTRL") (pin "5") (pinfunction "5_5") (pintype "passive"))
    )
    (net (code "72") (name "RST") (class "Default")
      (node (ref "CTRL") (pin "3") (pinfunction "3_3") (pintype "passive"))
    )
    (net (code "73") (name "SEL_ALU_A0") (class "Default")
      (node (ref "IN_SEL") (pin "2") (pinfunction "A_2") (pintype "input"))
      (node (ref "MICRO3,4") (pin "9") (pinfunction "9_9") (pintype "passive"))
    )
    (net (code "74") (name "SEL_ALU_A1") (class "Default")
      (node (ref "IN_SEL") (pin "3") (pinfunction "B_3") (pintype "input"))
      (node (ref "MICRO3,4") (pin "11") (pinfunction "11_11") (pintype "passive"))
    )
    (net (code "75") (name "SEL_ALU_B0") (class "Default")
      (node (ref "IN_SEL") (pin "14") (pinfunction "A_14") (pintype "input"))
      (node (ref "MICRO3,4") (pin "13") (pinfunction "13_13") (pintype "passive"))
    )
    (net (code "76") (name "SEL_ALU_B1") (class "Default")
      (node (ref "IN_SEL") (pin "13") (pinfunction "B_13") (pintype "input"))
      (node (ref "MICRO3,4") (pin "15") (pinfunction "15_15") (pintype "passive"))
    )
    (net (code "77") (name "STA0") (class "Default")
      (node (ref "BUFF_STA") (pin "2") (pinfunction "A1_2") (pintype "bidirectional"))
      (node (ref "STACK") (pin "2") (pinfunction "1Q_2") (pintype "output"))
    )
    (net (code "78") (name "STA1") (class "Default")
      (node (ref "BUFF_STA") (pin "3") (pinfunction "A2_3") (pintype "bidirectional"))
      (node (ref "STACK") (pin "5") (pinfunction "2Q_5") (pintype "output"))
    )
    (net (code "79") (name "STA2") (class "Default")
      (node (ref "BUFF_STA") (pin "4") (pinfunction "A3_4") (pintype "bidirectional"))
      (node (ref "STACK") (pin "6") (pinfunction "3Q_6") (pintype "output"))
    )
    (net (code "80") (name "STA3") (class "Default")
      (node (ref "BUFF_STA") (pin "5") (pinfunction "A4_5") (pintype "bidirectional"))
      (node (ref "STACK") (pin "9") (pinfunction "4Q_9") (pintype "output"))
    )
    (net (code "81") (name "STA4") (class "Default")
      (node (ref "BUFF_STA") (pin "6") (pinfunction "A5_6") (pintype "bidirectional"))
      (node (ref "STACK") (pin "12") (pinfunction "5Q_12") (pintype "output"))
    )
    (net (code "82") (name "STA5") (class "Default")
      (node (ref "BUFF_STA") (pin "7") (pinfunction "A6_7") (pintype "bidirectional"))
      (node (ref "STACK") (pin "15") (pinfunction "6Q_15") (pintype "output"))
    )
    (net (code "83") (name "STA6") (class "Default")
      (node (ref "BUFF_STA") (pin "8") (pinfunction "A7_8") (pintype "bidirectional"))
      (node (ref "STACK") (pin "16") (pinfunction "7Q_16") (pintype "output"))
    )
    (net (code "84") (name "STA7") (class "Default")
      (node (ref "BUFF_STA") (pin "9") (pinfunction "A8_9") (pintype "bidirectional"))
      (node (ref "STACK") (pin "19") (pinfunction "8Q_19") (pintype "output"))
    )
    (net (code "85") (name "SUB_B") (class "Default")
      (node (ref "2COMPL_1") (pin "10") (pinfunction "I1_10") (pintype "input"))
      (node (ref "2COMPL_1") (pin "13") (pinfunction "I1_13") (pintype "input"))
      (node (ref "2COMPL_1") (pin "2") (pinfunction "I1_2") (pintype "input"))
      (node (ref "2COMPL_1") (pin "5") (pinfunction "I1_5") (pintype "input"))
      (node (ref "2COMPL_2") (pin "10") (pinfunction "I1_10") (pintype "input"))
      (node (ref "2COMPL_2") (pin "13") (pinfunction "I1_13") (pintype "input"))
      (node (ref "2COMPL_2") (pin "2") (pinfunction "I1_2") (pintype "input"))
      (node (ref "2COMPL_2") (pin "5") (pinfunction "I1_5") (pintype "input"))
      (node (ref "MICRO3,4") (pin "6") (pinfunction "6_6") (pintype "passive"))
    )
    (net (code "86") (name "VCC") (class "Default")
      (node (ref "2COMPL_1") (pin "14") (pinfunction "VCC_14") (pintype "power_in"))
      (node (ref "BUFF_A1") (pin "1") (pinfunction "DIR_1") (pintype "input"))
      (node (ref "BUFF_A2") (pin "1") (pinfunction "DIR_1") (pintype "input"))
      (node (ref "BUFF_ALU") (pin "1") (pinfunction "DIR_1") (pintype "input"))
      (node (ref "BUFF_B1") (pin "1") (pinfunction "DIR_1") (pintype "input"))
      (node (ref "BUFF_B2") (pin "1") (pinfunction "DIR_1") (pintype "input"))
      (node (ref "BUFF_BUS") (pin "1") (pinfunction "DIR_1") (pintype "input"))
      (node (ref "BUFF_K") (pin "1") (pinfunction "DIR_1") (pintype "input"))
      (node (ref "BUFF_STA") (pin "1") (pinfunction "DIR_1") (pintype "input"))
      (node (ref "BUFF_Y") (pin "1") (pinfunction "DIR_1") (pintype "input"))
      (node (ref "C1") (pin "1") (pinfunction "1_1") (pintype "passive"))
      (node (ref "POWER") (pin "2") (pinfunction "2_2") (pintype "passive"))
    )
    (net (code "87") (name "Y0") (class "Default")
      (node (ref "BUFF_Y") (pin "2") (pinfunction "A1_2") (pintype "bidirectional"))
      (node (ref "REG_Y") (pin "2") (pinfunction "1Q_2") (pintype "output"))
    )
    (net (code "88") (name "Y1") (class "Default")
      (node (ref "BUFF_Y") (pin "3") (pinfunction "A2_3") (pintype "bidirectional"))
      (node (ref "REG_Y") (pin "5") (pinfunction "2Q_5") (pintype "output"))
    )
    (net (code "89") (name "Y2") (class "Default")
      (node (ref "BUFF_Y") (pin "4") (pinfunction "A3_4") (pintype "bidirectional"))
      (node (ref "REG_Y") (pin "6") (pinfunction "3Q_6") (pintype "output"))
    )
    (net (code "90") (name "Y3") (class "Default")
      (node (ref "BUFF_Y") (pin "5") (pinfunction "A4_5") (pintype "bidirectional"))
      (node (ref "REG_Y") (pin "9") (pinfunction "4Q_9") (pintype "output"))
    )
    (net (code "91") (name "Y4") (class "Default")
      (node (ref "BUFF_Y") (pin "6") (pinfunction "A5_6") (pintype "bidirectional"))
      (node (ref "REG_Y") (pin "12") (pinfunction "5Q_12") (pintype "output"))
    )
    (net (code "92") (name "Y5") (class "Default")
      (node (ref "BUFF_Y") (pin "7") (pinfunction "A6_7") (pintype "bidirectional"))
      (node (ref "REG_Y") (pin "15") (pinfunction "6Q_15") (pintype "output"))
    )
    (net (code "93") (name "Y6") (class "Default")
      (node (ref "BUFF_Y") (pin "8") (pinfunction "A7_8") (pintype "bidirectional"))
      (node (ref "REG_Y") (pin "16") (pinfunction "7Q_16") (pintype "output"))
    )
    (net (code "94") (name "Y7") (class "Default")
      (node (ref "BUFF_Y") (pin "9") (pinfunction "A8_9") (pintype "bidirectional"))
      (node (ref "REG_Y") (pin "19") (pinfunction "8Q_19") (pintype "output"))
    )
    (net (code "95") (name "unconnected-(AUX-Pad1)") (class "Default")
      (node (ref "AUX") (pin "1") (pinfunction "1_1") (pintype "passive"))
    )
    (net (code "96") (name "unconnected-(AUX-Pad2)") (class "Default")
      (node (ref "AUX") (pin "2") (pinfunction "2_2") (pintype "passive"))
    )
    (net (code "97") (name "unconnected-(AUX-Pad3)") (class "Default")
      (node (ref "AUX") (pin "3") (pinfunction "3_3") (pintype "passive"))
    )
    (net (code "98") (name "unconnected-(AUX-Pad4)") (class "Default")
      (node (ref "AUX") (pin "4") (pinfunction "4_4") (pintype "passive"))
    )
    (net (code "99") (name "unconnected-(AUX-Pad5)") (class "Default")
      (node (ref "AUX") (pin "5") (pinfunction "5_5") (pintype "passive"))
    )
    (net (code "100") (name "unconnected-(AUX-Pad6)") (class "Default")
      (node (ref "AUX") (pin "6") (pinfunction "6_6") (pintype "passive"))
    )
    (net (code "101") (name "unconnected-(AUX-Pad7)") (class "Default")
      (node (ref "AUX") (pin "7") (pinfunction "7_7") (pintype "passive"))
    )
    (net (code "102") (name "unconnected-(AUX-Pad8)") (class "Default")
      (node (ref "AUX") (pin "8") (pinfunction "8_8") (pintype "passive"))
    )
    (net (code "103") (name "unconnected-(AUX1-Pad1)") (class "Default")
      (node (ref "AUX1") (pin "1") (pinfunction "1_1") (pintype "passive"))
    )
    (net (code "104") (name "unconnected-(AUX1-Pad2)") (class "Default")
      (node (ref "AUX1") (pin "2") (pinfunction "2_2") (pintype "passive"))
    )
    (net (code "105") (name "unconnected-(AUX1-Pad3)") (class "Default")
      (node (ref "AUX1") (pin "3") (pinfunction "3_3") (pintype "passive"))
    )
    (net (code "106") (name "unconnected-(AUX1-Pad4)") (class "Default")
      (node (ref "AUX1") (pin "4") (pinfunction "4_4") (pintype "passive"))
    )
    (net (code "107") (name "unconnected-(AUX1-Pad5)") (class "Default")
      (node (ref "AUX1") (pin "5") (pinfunction "5_5") (pintype "passive"))
    )
    (net (code "108") (name "unconnected-(AUX1-Pad6)") (class "Default")
      (node (ref "AUX1") (pin "6") (pinfunction "6_6") (pintype "passive"))
    )
    (net (code "109") (name "unconnected-(AUX1-Pad7)") (class "Default")
      (node (ref "AUX1") (pin "7") (pinfunction "7_7") (pintype "passive"))
    )
    (net (code "110") (name "unconnected-(AUX1-Pad8)") (class "Default")
      (node (ref "AUX1") (pin "8") (pinfunction "8_8") (pintype "passive"))
    )
    (net (code "111") (name "unconnected-(AUX2-Pad1)") (class "Default")
      (node (ref "AUX2") (pin "1") (pinfunction "1_1") (pintype "passive"))
    )
    (net (code "112") (name "unconnected-(AUX2-Pad2)") (class "Default")
      (node (ref "AUX2") (pin "2") (pinfunction "2_2") (pintype "passive"))
    )
    (net (code "113") (name "unconnected-(AUX2-Pad3)") (class "Default")
      (node (ref "AUX2") (pin "3") (pinfunction "3_3") (pintype "passive"))
    )
    (net (code "114") (name "unconnected-(AUX2-Pad4)") (class "Default")
      (node (ref "AUX2") (pin "4") (pinfunction "4_4") (pintype "passive"))
    )
    (net (code "115") (name "unconnected-(AUX2-Pad5)") (class "Default")
      (node (ref "AUX2") (pin "5") (pinfunction "5_5") (pintype "passive"))
    )
    (net (code "116") (name "unconnected-(AUX2-Pad6)") (class "Default")
      (node (ref "AUX2") (pin "6") (pinfunction "6_6") (pintype "passive"))
    )
    (net (code "117") (name "unconnected-(AUX2-Pad7)") (class "Default")
      (node (ref "AUX2") (pin "7") (pinfunction "7_7") (pintype "passive"))
    )
    (net (code "118") (name "unconnected-(AUX2-Pad8)") (class "Default")
      (node (ref "AUX2") (pin "8") (pinfunction "8_8") (pintype "passive"))
    )
    (net (code "119") (name "unconnected-(AUX3-Pad1)") (class "Default")
      (node (ref "AUX3") (pin "1") (pinfunction "1_1") (pintype "passive"))
    )
    (net (code "120") (name "unconnected-(AUX3-Pad2)") (class "Default")
      (node (ref "AUX3") (pin "2") (pinfunction "2_2") (pintype "passive"))
    )
    (net (code "121") (name "unconnected-(AUX3-Pad3)") (class "Default")
      (node (ref "AUX3") (pin "3") (pinfunction "3_3") (pintype "passive"))
    )
    (net (code "122") (name "unconnected-(AUX3-Pad4)") (class "Default")
      (node (ref "AUX3") (pin "4") (pinfunction "4_4") (pintype "passive"))
    )
    (net (code "123") (name "unconnected-(AUX3-Pad5)") (class "Default")
      (node (ref "AUX3") (pin "5") (pinfunction "5_5") (pintype "passive"))
    )
    (net (code "124") (name "unconnected-(AUX3-Pad6)") (class "Default")
      (node (ref "AUX3") (pin "6") (pinfunction "6_6") (pintype "passive"))
    )
    (net (code "125") (name "unconnected-(AUX3-Pad7)") (class "Default")
      (node (ref "AUX3") (pin "7") (pinfunction "7_7") (pintype "passive"))
    )
    (net (code "126") (name "unconnected-(AUX3-Pad8)") (class "Default")
      (node (ref "AUX3") (pin "8") (pinfunction "8_8") (pintype "passive"))
    )
    (net (code "127") (name "unconnected-(AUX4-Pad1)") (class "Default")
      (node (ref "AUX4") (pin "1") (pinfunction "1_1") (pintype "passive"))
    )
    (net (code "128") (name "unconnected-(AUX4-Pad2)") (class "Default")
      (node (ref "AUX4") (pin "2") (pinfunction "2_2") (pintype "passive"))
    )
    (net (code "129") (name "unconnected-(AUX4-Pad3)") (class "Default")
      (node (ref "AUX4") (pin "3") (pinfunction "3_3") (pintype "passive"))
    )
    (net (code "130") (name "unconnected-(AUX4-Pad4)") (class "Default")
      (node (ref "AUX4") (pin "4") (pinfunction "4_4") (pintype "passive"))
    )
    (net (code "131") (name "unconnected-(AUX4-Pad5)") (class "Default")
      (node (ref "AUX4") (pin "5") (pinfunction "5_5") (pintype "passive"))
    )
    (net (code "132") (name "unconnected-(AUX4-Pad6)") (class "Default")
      (node (ref "AUX4") (pin "6") (pinfunction "6_6") (pintype "passive"))
    )
    (net (code "133") (name "unconnected-(AUX4-Pad7)") (class "Default")
      (node (ref "AUX4") (pin "7") (pinfunction "7_7") (pintype "passive"))
    )
    (net (code "134") (name "unconnected-(AUX4-Pad8)") (class "Default")
      (node (ref "AUX4") (pin "8") (pinfunction "8_8") (pintype "passive"))
    )
    (net (code "135") (name "unconnected-(CTRL-Pad8)") (class "Default")
      (node (ref "CTRL") (pin "8") (pinfunction "8_8") (pintype "passive"))
    )
    (net (code "136") (name "unconnected-(FLAGS-Pad7)") (class "Default")
      (node (ref "FLAGS") (pin "7") (pinfunction "7_7") (pintype "passive"))
    )
    (net (code "137") (name "unconnected-(FLAGS-Pad8)") (class "Default")
      (node (ref "FLAGS") (pin "8") (pinfunction "8_8") (pintype "passive"))
    )
    (net (code "138") (name "unconnected-(MICRO1,2-Pad2)") (class "Default")
      (node (ref "MICRO1,2") (pin "2") (pinfunction "2_2") (pintype "passive"))
    )
    (net (code "139") (name "unconnected-(MICRO1,2-Pad4)") (class "Default")
      (node (ref "MICRO1,2") (pin "4") (pinfunction "4_4") (pintype "passive"))
    )
    (net (code "140") (name "unconnected-(MICRO1,2-Pad6)") (class "Default")
      (node (ref "MICRO1,2") (pin "6") (pinfunction "6_6") (pintype "passive"))
    )
    (net (code "141") (name "unconnected-(MICRO1,2-Pad8)") (class "Default")
      (node (ref "MICRO1,2") (pin "8") (pinfunction "8_8") (pintype "passive"))
    )
    (net (code "142") (name "unconnected-(MICRO1,2-Pad10)") (class "Default")
      (node (ref "MICRO1,2") (pin "10") (pinfunction "10_10") (pintype "passive"))
    )
    (net (code "143") (name "unconnected-(MICRO1,2-Pad16)") (class "Default")
      (node (ref "MICRO1,2") (pin "16") (pinfunction "16_16") (pintype "passive"))
    )
    (net (code "144") (name "unconnected-(MICRO3,4-Pad10)") (class "Default")
      (node (ref "MICRO3,4") (pin "10") (pinfunction "10_10") (pintype "passive"))
    )
    (net (code "145") (name "unconnected-(MICRO5,6-Pad1)") (class "Default")
      (node (ref "MICRO5,6") (pin "1") (pinfunction "1_1") (pintype "passive"))
    )
    (net (code "146") (name "unconnected-(MICRO5,6-Pad2)") (class "Default")
      (node (ref "MICRO5,6") (pin "2") (pinfunction "2_2") (pintype "passive"))
    )
    (net (code "147") (name "unconnected-(MICRO5,6-Pad3)") (class "Default")
      (node (ref "MICRO5,6") (pin "3") (pinfunction "3_3") (pintype "passive"))
    )
    (net (code "148") (name "unconnected-(MICRO5,6-Pad4)") (class "Default")
      (node (ref "MICRO5,6") (pin "4") (pinfunction "4_4") (pintype "passive"))
    )
    (net (code "149") (name "unconnected-(MICRO5,6-Pad5)") (class "Default")
      (node (ref "MICRO5,6") (pin "5") (pinfunction "5_5") (pintype "passive"))
    )
    (net (code "150") (name "unconnected-(MICRO5,6-Pad6)") (class "Default")
      (node (ref "MICRO5,6") (pin "6") (pinfunction "6_6") (pintype "passive"))
    )
    (net (code "151") (name "unconnected-(MICRO5,6-Pad7)") (class "Default")
      (node (ref "MICRO5,6") (pin "7") (pinfunction "7_7") (pintype "passive"))
    )
    (net (code "152") (name "unconnected-(MICRO5,6-Pad8)") (class "Default")
      (node (ref "MICRO5,6") (pin "8") (pinfunction "8_8") (pintype "passive"))
    )
    (net (code "153") (name "unconnected-(MICRO5,6-Pad9)") (class "Default")
      (node (ref "MICRO5,6") (pin "9") (pinfunction "9_9") (pintype "passive"))
    )
    (net (code "154") (name "unconnected-(MICRO5,6-Pad10)") (class "Default")
      (node (ref "MICRO5,6") (pin "10") (pinfunction "10_10") (pintype "passive"))
    )
    (net (code "155") (name "unconnected-(MICRO5,6-Pad11)") (class "Default")
      (node (ref "MICRO5,6") (pin "11") (pinfunction "11_11") (pintype "passive"))
    )
    (net (code "156") (name "unconnected-(MICRO5,6-Pad12)") (class "Default")
      (node (ref "MICRO5,6") (pin "12") (pinfunction "12_12") (pintype "passive"))
    )
    (net (code "157") (name "unconnected-(MICRO5,6-Pad13)") (class "Default")
      (node (ref "MICRO5,6") (pin "13") (pinfunction "13_13") (pintype "passive"))
    )
    (net (code "158") (name "unconnected-(MICRO5,6-Pad14)") (class "Default")
      (node (ref "MICRO5,6") (pin "14") (pinfunction "14_14") (pintype "passive"))
    )
    (net (code "159") (name "unconnected-(MICRO5,6-Pad15)") (class "Default")
      (node (ref "MICRO5,6") (pin "15") (pinfunction "15_15") (pintype "passive"))
    )
    (net (code "160") (name "unconnected-(MICRO5,6-Pad16)") (class "Default")
      (node (ref "MICRO5,6") (pin "16") (pinfunction "16_16") (pintype "passive"))
    )
    (net (code "161") (name "~{CLK}") (class "Default")
      (node (ref "CTRL") (pin "2") (pinfunction "2_2") (pintype "passive"))
    )
    (net (code "162") (name "~{FL_C}") (class "Default")
      (node (ref "FLAGS") (pin "6") (pinfunction "6_6") (pintype "passive"))
    )
    (net (code "163") (name "~{FL_N}") (class "Default")
      (node (ref "FLAGS") (pin "4") (pinfunction "4_4") (pintype "passive"))
    )
    (net (code "164") (name "~{FL_Z}") (class "Default")
      (node (ref "FLAGS") (pin "2") (pinfunction "2_2") (pintype "passive"))
    )
    (net (code "165") (name "~{HALT}") (class "Default")
      (node (ref "MICRO1,2") (pin "15") (pinfunction "15_15") (pintype "passive"))
    )
    (net (code "166") (name "~{PROG}") (class "Default")
      (node (ref "CTRL") (pin "6") (pinfunction "6_6") (pintype "passive"))
    )
    (net (code "167") (name "~{RD_A1}") (class "Default")
      (node (ref "BUFF_A1") (pin "19") (pinfunction "G_19") (pintype "input"))
      (node (ref "IN_SEL") (pin "4") (pinfunction "Y0_4") (pintype "output"))
    )
    (net (code "168") (name "~{RD_A2}") (class "Default")
      (node (ref "BUFF_A2") (pin "19") (pinfunction "G_19") (pintype "input"))
      (node (ref "IN_SEL") (pin "12") (pinfunction "Y0_12") (pintype "output"))
    )
    (net (code "169") (name "~{RD_ALU}") (class "Default")
      (node (ref "BUFF_ALU") (pin "19") (pinfunction "G_19") (pintype "input"))
      (node (ref "MICRO3,4") (pin "2") (pinfunction "2_2") (pintype "passive"))
    )
    (net (code "170") (name "~{RD_B1}") (class "Default")
      (node (ref "BUFF_B1") (pin "19") (pinfunction "G_19") (pintype "input"))
      (node (ref "IN_SEL") (pin "5") (pinfunction "Y1_5") (pintype "output"))
    )
    (net (code "171") (name "~{RD_B2}") (class "Default")
      (node (ref "BUFF_B2") (pin "19") (pinfunction "G_19") (pintype "input"))
      (node (ref "IN_SEL") (pin "11") (pinfunction "Y1_11") (pintype "output"))
    )
    (net (code "172") (name "~{RD_BUS}") (class "Default")
      (node (ref "BUFF_BUS") (pin "19") (pinfunction "G_19") (pintype "input"))
      (node (ref "IN_SEL") (pin "9") (pinfunction "Y3_9") (pintype "output"))
    )
    (net (code "173") (name "~{RD_K}") (class "Default")
      (node (ref "BUFF_K") (pin "19") (pinfunction "G_19") (pintype "input"))
      (node (ref "IN_SEL") (pin "10") (pinfunction "Y2_10") (pintype "output"))
    )
    (net (code "174") (name "~{RD_PC}") (class "Default")
      (node (ref "MICRO1,2") (pin "3") (pinfunction "3_3") (pintype "passive"))
    )
    (net (code "175") (name "~{RD_ROM}") (class "Default")
      (node (ref "MICRO1,2") (pin "9") (pinfunction "9_9") (pintype "passive"))
    )
    (net (code "176") (name "~{RD_STACK}") (class "Default")
      (node (ref "BUFF_STA") (pin "19") (pinfunction "G_19") (pintype "input"))
      (node (ref "IN_SEL") (pin "7") (pinfunction "Y3_7") (pintype "output"))
    )
    (net (code "177") (name "~{RD_Y}") (class "Default")
      (node (ref "BUFF_Y") (pin "19") (pinfunction "G_19") (pintype "input"))
      (node (ref "IN_SEL") (pin "6") (pinfunction "Y2_6") (pintype "output"))
    )
    (net (code "178") (name "~{RST}") (class "Default")
      (node (ref "CTRL") (pin "4") (pinfunction "4_4") (pintype "passive"))
    )
    (net (code "179") (name "~{WR_A}") (class "Default")
      (node (ref "MICRO3,4") (pin "1") (pinfunction "1_1") (pintype "passive"))
      (node (ref "REG_A") (pin "1") (pinfunction "G_1") (pintype "input"))
    )
    (net (code "180") (name "~{WR_B}") (class "Default")
      (node (ref "MICRO3,4") (pin "3") (pinfunction "3_3") (pintype "passive"))
      (node (ref "REG_B") (pin "1") (pinfunction "G_1") (pintype "input"))
    )
    (net (code "181") (name "~{WR_FL}") (class "Default")
      (node (ref "MICRO3,4") (pin "4") (pinfunction "4_4") (pintype "passive"))
    )
    (net (code "182") (name "~{WR_IR}") (class "Default")
      (node (ref "MICRO1,2") (pin "11") (pinfunction "11_11") (pintype "passive"))
    )
    (net (code "183") (name "~{WR_MAR}") (class "Default")
      (node (ref "MICRO1,2") (pin "5") (pinfunction "5_5") (pintype "passive"))
    )
    (net (code "184") (name "~{WR_OUT}") (class "Default")
      (node (ref "MICRO1,2") (pin "13") (pinfunction "13_13") (pintype "passive"))
    )
    (net (code "185") (name "~{WR_ROM}") (class "Default")
      (node (ref "MICRO1,2") (pin "7") (pinfunction "7_7") (pintype "passive"))
    )
    (net (code "186") (name "~{WR_STACK}") (class "Default")
      (node (ref "MICRO3,4") (pin "7") (pinfunction "7_7") (pintype "passive"))
      (node (ref "STACK") (pin "1") (pinfunction "G_1") (pintype "input"))
    )
    (net (code "187") (name "~{WR_Y}") (class "Default")
      (node (ref "MICRO3,4") (pin "5") (pinfunction "5_5") (pintype "passive"))
      (node (ref "REG_Y") (pin "1") (pinfunction "G_1") (pintype "input"))
    )
  )
)
